# raspberry-pi-interface-board.net
KiCad netlist of a schematic drawn in EAGLE
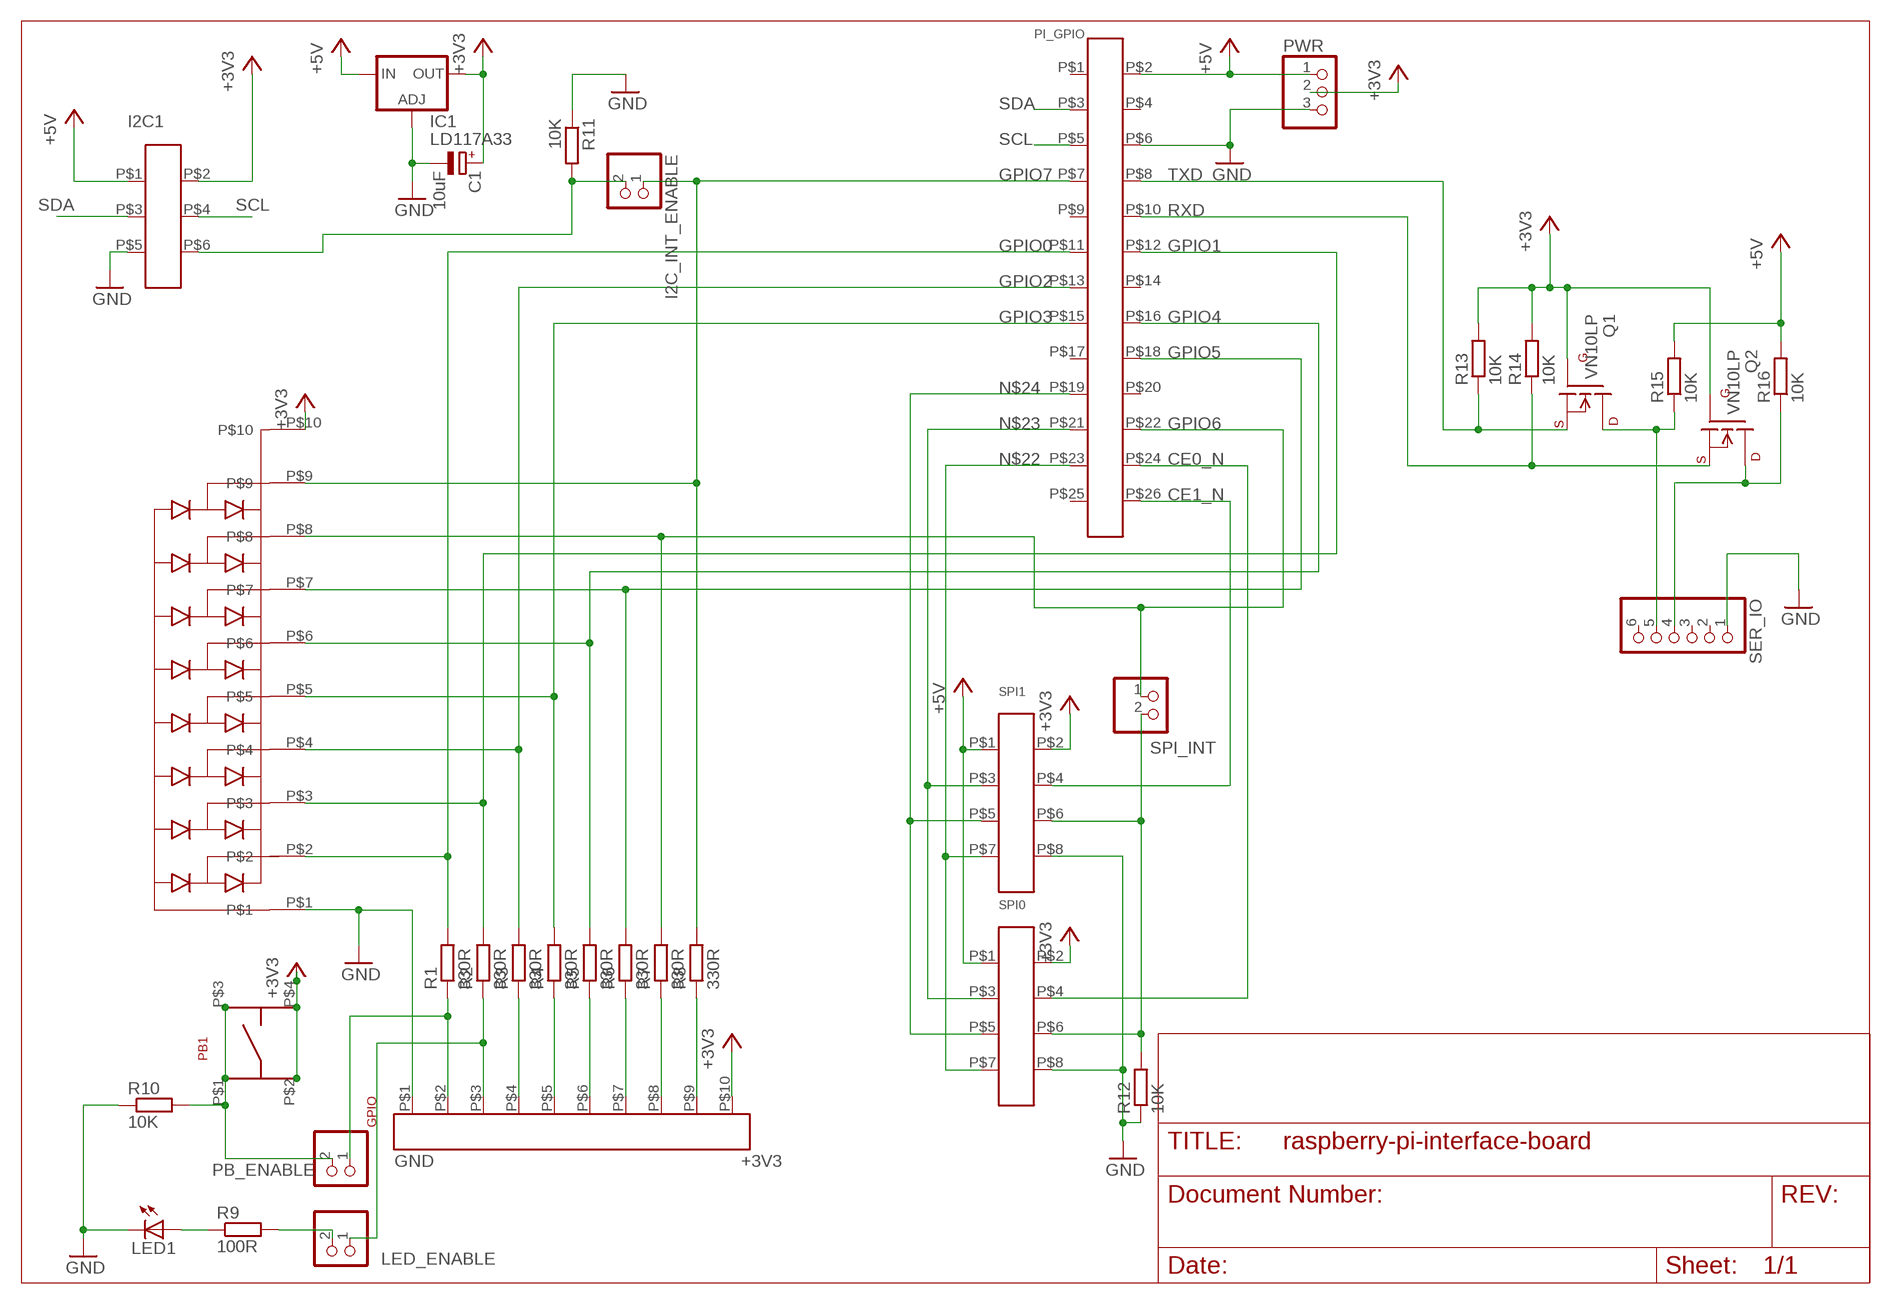
[diagram p0: schematic, sheet 1]

(export (version "E")
  (design (tool "Eeschema 10.0.6"))
  (components
    (comp (ref "C1")
      (value "10uF")
      (footprint "eagle-import:E2,5-7")
      (libsource (lib "eagle-import") (part "CPOL-EUE2.5-7"))
    )
    (comp (ref "GPIO")
      (value "APM-10W-SOCKET")
      (footprint "eagle-import:AMP-10W-SOCKET")
      (libsource (lib "eagle-import") (part "APM-10W-SOCKET"))
    )
    (comp (ref "I2C1")
      (value "IC2_0")
      (footprint "eagle-import:IDC-6W")
      (libsource (lib "eagle-import") (part "IDC-6W"))
    )
    (comp (ref "I2C_INT_ENABLE")
      (value "PINHD-1X2")
      (footprint "eagle-import:1X02")
      (libsource (lib "eagle-import") (part "PINHD-1X2"))
    )
    (comp (ref "IC1")
      (value "LD117A33")
      (footprint "eagle-import:TO220S")
      (libsource (lib "eagle-import") (part "LD117A?33"))
    )
    (comp (ref "LED1")
      (value "LED3MM")
      (footprint "eagle-import:LED3MM")
      (libsource (lib "eagle-import") (part "LED3MM"))
    )
    (comp (ref "LED_ENABLE")
      (value "PINHD-1X2")
      (footprint "eagle-import:1X02")
      (libsource (lib "eagle-import") (part "PINHD-1X2"))
    )
    (comp (ref "PB1")
      (value "TYCO-PUSHBUTTON")
      (footprint "eagle-import:TYCO-PUSHBUTTON")
      (libsource (lib "eagle-import") (part "TYCO-PUSHBUTTON"))
    )
    (comp (ref "PB_ENABLE")
      (value "PINHD-1X2")
      (footprint "eagle-import:1X02")
      (libsource (lib "eagle-import") (part "PINHD-1X2"))
    )
    (comp (ref "PI_GPIO")
      (value "IDC-26W")
      (footprint "eagle-import:IDC-26W")
      (libsource (lib "eagle-import") (part "IDC-26W"))
    )
    (comp (ref "PWR")
      (value "PINHD-1X3")
      (footprint "eagle-import:1X03")
      (libsource (lib "eagle-import") (part "PINHD-1X3"))
    )
    (comp (ref "Q1")
      (value "VN10LP")
      (footprint "eagle-import:TO92")
      (libsource (lib "eagle-import") (part "VN10LP"))
    )
    (comp (ref "Q2")
      (value "VN10LP")
      (footprint "eagle-import:TO92")
      (libsource (lib "eagle-import") (part "VN10LP"))
    )
    (comp (ref "R1")
      (value "330R")
      (footprint "eagle-import:0204_7")
      (libsource (lib "eagle-import") (part "R-EU_0204/7"))
    )
    (comp (ref "R2")
      (value "330R")
      (footprint "eagle-import:0204_7")
      (libsource (lib "eagle-import") (part "R-EU_0204/7"))
    )
    (comp (ref "R3")
      (value "330R")
      (footprint "eagle-import:0204_7")
      (libsource (lib "eagle-import") (part "R-EU_0204/7"))
    )
    (comp (ref "R4")
      (value "330R")
      (footprint "eagle-import:0204_7")
      (libsource (lib "eagle-import") (part "R-EU_0204/7"))
    )
    (comp (ref "R5")
      (value "330R")
      (footprint "eagle-import:0204_7")
      (libsource (lib "eagle-import") (part "R-EU_0204/7"))
    )
    (comp (ref "R6")
      (value "330R")
      (footprint "eagle-import:0204_7")
      (libsource (lib "eagle-import") (part "R-EU_0204/7"))
    )
    (comp (ref "R7")
      (value "330R")
      (footprint "eagle-import:0204_7")
      (libsource (lib "eagle-import") (part "R-EU_0204/7"))
    )
    (comp (ref "R8")
      (value "330R")
      (footprint "eagle-import:0204_7")
      (libsource (lib "eagle-import") (part "R-EU_0204/7"))
    )
    (comp (ref "R9")
      (value "100R")
      (footprint "eagle-import:0207_10")
      (libsource (lib "eagle-import") (part "R-EU_0207/10"))
    )
    (comp (ref "R10")
      (value "10K")
      (footprint "eagle-import:0207_10")
      (libsource (lib "eagle-import") (part "R-EU_0207/10"))
    )
    (comp (ref "R11")
      (value "10K")
      (footprint "eagle-import:0207_10")
      (libsource (lib "eagle-import") (part "R-EU_0207/10"))
    )
    (comp (ref "R12")
      (value "10K")
      (footprint "eagle-import:0207_10")
      (libsource (lib "eagle-import") (part "R-EU_0207/10"))
    )
    (comp (ref "R13")
      (value "10K")
      (footprint "eagle-import:0207_10")
      (libsource (lib "eagle-import") (part "R-EU_0207/10"))
    )
    (comp (ref "R14")
      (value "10K")
      (footprint "eagle-import:0207_10")
      (libsource (lib "eagle-import") (part "R-EU_0207/10"))
    )
    (comp (ref "R15")
      (value "10K")
      (footprint "eagle-import:0207_10")
      (libsource (lib "eagle-import") (part "R-EU_0207/10"))
    )
    (comp (ref "R16")
      (value "10K")
      (footprint "eagle-import:0207_10")
      (libsource (lib "eagle-import") (part "R-EU_0207/10"))
    )
    (comp (ref "SER_IO")
      (value "PINHD-1X6")
      (footprint "eagle-import:1X06")
      (libsource (lib "eagle-import") (part "PINHD-1X6"))
    )
    (comp (ref "SPI0")
      (value "IDC-8W")
      (footprint "eagle-import:IDC-8W")
      (libsource (lib "eagle-import") (part "IDC-8W"))
    )
    (comp (ref "SPI1")
      (value "IDC-8W")
      (footprint "eagle-import:IDC-8W")
      (libsource (lib "eagle-import") (part "IDC-8W"))
    )
    (comp (ref "SPI_INT")
      (value "PINHD-1X2")
      (footprint "eagle-import:1X02")
      (libsource (lib "eagle-import") (part "PINHD-1X2"))
    )
    (comp (ref "U$2")
      (value "D10-5A")
      (footprint "eagle-import:D10-5A")
      (libsource (lib "eagle-import") (part "D10-5A"))
    )
  )
  (nets
    (net (code "1") (name "+3V3") (class "Default")
      (node (ref "C1") (pin "+") (pinfunction "+_+") (pintype "passive"))
      (node (ref "GPIO") (pin "P$10") (pinfunction "P$10_P$10") (pintype "bidirectional"))
      (node (ref "I2C1") (pin "P$2") (pinfunction "P$2_P$2") (pintype "bidirectional"))
      (node (ref "IC1") (pin "2") (pinfunction "OUT_2") (pintype "passive"))
      (node (ref "PB1") (pin "P$2") (pinfunction "P$2_P$2") (pintype "bidirectional"))
      (node (ref "PB1") (pin "P$4") (pinfunction "P$4_P$4") (pintype "bidirectional"))
      (node (ref "PWR") (pin "2") (pinfunction "2_2") (pintype "passive"))
      (node (ref "Q1") (pin "2") (pinfunction "G_2") (pintype "passive"))
      (node (ref "Q2") (pin "2") (pinfunction "G_2") (pintype "passive"))
      (node (ref "R13") (pin "2") (pinfunction "2_2") (pintype "passive"))
      (node (ref "R14") (pin "2") (pinfunction "2_2") (pintype "passive"))
      (node (ref "SPI0") (pin "P$2") (pinfunction "P$2_P$2") (pintype "bidirectional"))
      (node (ref "SPI1") (pin "P$2") (pinfunction "P$2_P$2") (pintype "bidirectional"))
      (node (ref "U$2") (pin "P$10") (pinfunction "P$10_P$10") (pintype "power_in"))
    )
    (net (code "2") (name "+5V") (class "Default")
      (node (ref "I2C1") (pin "P$1") (pinfunction "P$1_P$1") (pintype "bidirectional"))
      (node (ref "IC1") (pin "3") (pinfunction "IN_3") (pintype "input"))
      (node (ref "PI_GPIO") (pin "P$2") (pinfunction "P$2_P$2") (pintype "bidirectional"))
      (node (ref "PWR") (pin "1") (pinfunction "1_1") (pintype "passive"))
      (node (ref "R15") (pin "2") (pinfunction "2_2") (pintype "passive"))
      (node (ref "R16") (pin "2") (pinfunction "2_2") (pintype "passive"))
      (node (ref "SPI0") (pin "P$1") (pinfunction "P$1_P$1") (pintype "bidirectional"))
      (node (ref "SPI1") (pin "P$1") (pinfunction "P$1_P$1") (pintype "bidirectional"))
    )
    (net (code "3") (name "/CE0_N") (class "Default")
      (node (ref "PI_GPIO") (pin "P$24") (pinfunction "P$24_P$24") (pintype "bidirectional"))
      (node (ref "SPI0") (pin "P$4") (pinfunction "P$4_P$4") (pintype "bidirectional"))
    )
    (net (code "4") (name "/CE1_N") (class "Default")
      (node (ref "PI_GPIO") (pin "P$26") (pinfunction "P$26_P$26") (pintype "bidirectional"))
      (node (ref "SPI1") (pin "P$4") (pinfunction "P$4_P$4") (pintype "bidirectional"))
    )
    (net (code "5") (name "/GPIO0") (class "Default")
      (node (ref "PI_GPIO") (pin "P$11") (pinfunction "P$11_P$11") (pintype "bidirectional"))
      (node (ref "R1") (pin "2") (pinfunction "2_2") (pintype "passive"))
      (node (ref "U$2") (pin "P$2") (pinfunction "P$2_P$2") (pintype "bidirectional"))
    )
    (net (code "6") (name "/GPIO1") (class "Default")
      (node (ref "PI_GPIO") (pin "P$12") (pinfunction "P$12_P$12") (pintype "bidirectional"))
      (node (ref "R2") (pin "2") (pinfunction "2_2") (pintype "passive"))
      (node (ref "U$2") (pin "P$3") (pinfunction "P$3_P$3") (pintype "bidirectional"))
    )
    (net (code "7") (name "/GPIO2") (class "Default")
      (node (ref "PI_GPIO") (pin "P$13") (pinfunction "P$13_P$13") (pintype "bidirectional"))
      (node (ref "R3") (pin "2") (pinfunction "2_2") (pintype "passive"))
      (node (ref "U$2") (pin "P$4") (pinfunction "P$4_P$4") (pintype "bidirectional"))
    )
    (net (code "8") (name "/GPIO3") (class "Default")
      (node (ref "PI_GPIO") (pin "P$15") (pinfunction "P$15_P$15") (pintype "bidirectional"))
      (node (ref "R4") (pin "2") (pinfunction "2_2") (pintype "passive"))
      (node (ref "U$2") (pin "P$5") (pinfunction "P$5_P$5") (pintype "bidirectional"))
    )
    (net (code "9") (name "/GPIO4") (class "Default")
      (node (ref "PI_GPIO") (pin "P$16") (pinfunction "P$16_P$16") (pintype "bidirectional"))
      (node (ref "R5") (pin "2") (pinfunction "2_2") (pintype "passive"))
      (node (ref "U$2") (pin "P$6") (pinfunction "P$6_P$6") (pintype "bidirectional"))
    )
    (net (code "10") (name "/GPIO5") (class "Default")
      (node (ref "PI_GPIO") (pin "P$18") (pinfunction "P$18_P$18") (pintype "bidirectional"))
      (node (ref "R6") (pin "2") (pinfunction "2_2") (pintype "passive"))
      (node (ref "U$2") (pin "P$7") (pinfunction "P$7_P$7") (pintype "bidirectional"))
    )
    (net (code "11") (name "/GPIO6") (class "Default")
      (node (ref "PI_GPIO") (pin "P$22") (pinfunction "P$22_P$22") (pintype "bidirectional"))
      (node (ref "R7") (pin "2") (pinfunction "2_2") (pintype "passive"))
      (node (ref "SPI_INT") (pin "1") (pinfunction "1_1") (pintype "passive"))
      (node (ref "U$2") (pin "P$8") (pinfunction "P$8_P$8") (pintype "bidirectional"))
    )
    (net (code "12") (name "/GPIO7") (class "Default")
      (node (ref "I2C_INT_ENABLE") (pin "1") (pinfunction "1_1") (pintype "passive"))
      (node (ref "PI_GPIO") (pin "P$7") (pinfunction "P$7_P$7") (pintype "bidirectional"))
      (node (ref "R8") (pin "2") (pinfunction "2_2") (pintype "passive"))
      (node (ref "U$2") (pin "P$9") (pinfunction "P$9_P$9") (pintype "bidirectional"))
    )
    (net (code "13") (name "/N$22") (class "Default")
      (node (ref "PI_GPIO") (pin "P$23") (pinfunction "P$23_P$23") (pintype "bidirectional"))
      (node (ref "SPI0") (pin "P$7") (pinfunction "P$7_P$7") (pintype "bidirectional"))
      (node (ref "SPI1") (pin "P$7") (pinfunction "P$7_P$7") (pintype "bidirectional"))
    )
    (net (code "14") (name "/N$23") (class "Default")
      (node (ref "PI_GPIO") (pin "P$21") (pinfunction "P$21_P$21") (pintype "bidirectional"))
      (node (ref "SPI0") (pin "P$3") (pinfunction "P$3_P$3") (pintype "bidirectional"))
      (node (ref "SPI1") (pin "P$3") (pinfunction "P$3_P$3") (pintype "bidirectional"))
    )
    (net (code "15") (name "/N$24") (class "Default")
      (node (ref "PI_GPIO") (pin "P$19") (pinfunction "P$19_P$19") (pintype "bidirectional"))
      (node (ref "SPI0") (pin "P$5") (pinfunction "P$5_P$5") (pintype "bidirectional"))
      (node (ref "SPI1") (pin "P$5") (pinfunction "P$5_P$5") (pintype "bidirectional"))
    )
    (net (code "16") (name "/RXD") (class "Default")
      (node (ref "PI_GPIO") (pin "P$10") (pinfunction "P$10_P$10") (pintype "bidirectional"))
      (node (ref "Q2") (pin "3") (pinfunction "S_3") (pintype "passive"))
      (node (ref "R14") (pin "1") (pinfunction "1_1") (pintype "passive"))
    )
    (net (code "17") (name "/SCL") (class "Default")
      (node (ref "I2C1") (pin "P$4") (pinfunction "P$4_P$4") (pintype "bidirectional"))
      (node (ref "PI_GPIO") (pin "P$5") (pinfunction "P$5_P$5") (pintype "bidirectional"))
    )
    (net (code "18") (name "/SDA") (class "Default")
      (node (ref "I2C1") (pin "P$3") (pinfunction "P$3_P$3") (pintype "bidirectional"))
      (node (ref "PI_GPIO") (pin "P$3") (pinfunction "P$3_P$3") (pintype "bidirectional"))
    )
    (net (code "19") (name "/TXD") (class "Default")
      (node (ref "PI_GPIO") (pin "P$8") (pinfunction "P$8_P$8") (pintype "bidirectional"))
      (node (ref "Q1") (pin "3") (pinfunction "S_3") (pintype "passive"))
      (node (ref "R13") (pin "1") (pinfunction "1_1") (pintype "passive"))
    )
    (net (code "20") (name "GND") (class "Default")
      (node (ref "C1") (pin "-") (pinfunction "-_-") (pintype "passive"))
      (node (ref "GPIO") (pin "P$1") (pinfunction "P$1_P$1") (pintype "bidirectional"))
      (node (ref "I2C1") (pin "P$5") (pinfunction "P$5_P$5") (pintype "bidirectional"))
      (node (ref "IC1") (pin "1") (pinfunction "ADJ_1") (pintype "input"))
      (node (ref "LED1") (pin "K") (pinfunction "C_K") (pintype "passive"))
      (node (ref "PI_GPIO") (pin "P$6") (pinfunction "P$6_P$6") (pintype "bidirectional"))
      (node (ref "PWR") (pin "3") (pinfunction "3_3") (pintype "passive"))
      (node (ref "R10") (pin "1") (pinfunction "1_1") (pintype "passive"))
      (node (ref "R11") (pin "1") (pinfunction "1_1") (pintype "passive"))
      (node (ref "R12") (pin "1") (pinfunction "1_1") (pintype "passive"))
      (node (ref "SER_IO") (pin "1") (pinfunction "1_1") (pintype "passive"))
      (node (ref "SPI0") (pin "P$8") (pinfunction "P$8_P$8") (pintype "bidirectional"))
      (node (ref "SPI1") (pin "P$8") (pinfunction "P$8_P$8") (pintype "bidirectional"))
      (node (ref "U$2") (pin "P$1") (pinfunction "P$1_P$1") (pintype "power_in"))
    )
    (net (code "21") (name "Net-(GPIO-PadP$2)") (class "Default")
      (node (ref "GPIO") (pin "P$2") (pinfunction "P$2_P$2") (pintype "bidirectional"))
      (node (ref "PB_ENABLE") (pin "1") (pinfunction "1_1") (pintype "passive"))
      (node (ref "R1") (pin "1") (pinfunction "1_1") (pintype "passive"))
    )
    (net (code "22") (name "Net-(GPIO-PadP$3)") (class "Default")
      (node (ref "GPIO") (pin "P$3") (pinfunction "P$3_P$3") (pintype "bidirectional"))
      (node (ref "LED_ENABLE") (pin "1") (pinfunction "1_1") (pintype "passive"))
      (node (ref "R2") (pin "1") (pinfunction "1_1") (pintype "passive"))
    )
    (net (code "23") (name "Net-(GPIO-PadP$4)") (class "Default")
      (node (ref "GPIO") (pin "P$4") (pinfunction "P$4_P$4") (pintype "bidirectional"))
      (node (ref "R3") (pin "1") (pinfunction "1_1") (pintype "passive"))
    )
    (net (code "24") (name "Net-(GPIO-PadP$5)") (class "Default")
      (node (ref "GPIO") (pin "P$5") (pinfunction "P$5_P$5") (pintype "bidirectional"))
      (node (ref "R4") (pin "1") (pinfunction "1_1") (pintype "passive"))
    )
    (net (code "25") (name "Net-(GPIO-PadP$6)") (class "Default")
      (node (ref "GPIO") (pin "P$6") (pinfunction "P$6_P$6") (pintype "bidirectional"))
      (node (ref "R5") (pin "1") (pinfunction "1_1") (pintype "passive"))
    )
    (net (code "26") (name "Net-(GPIO-PadP$7)") (class "Default")
      (node (ref "GPIO") (pin "P$7") (pinfunction "P$7_P$7") (pintype "bidirectional"))
      (node (ref "R6") (pin "1") (pinfunction "1_1") (pintype "passive"))
    )
    (net (code "27") (name "Net-(GPIO-PadP$8)") (class "Default")
      (node (ref "GPIO") (pin "P$8") (pinfunction "P$8_P$8") (pintype "bidirectional"))
      (node (ref "R7") (pin "1") (pinfunction "1_1") (pintype "passive"))
    )
    (net (code "28") (name "Net-(GPIO-PadP$9)") (class "Default")
      (node (ref "GPIO") (pin "P$9") (pinfunction "P$9_P$9") (pintype "bidirectional"))
      (node (ref "R8") (pin "1") (pinfunction "1_1") (pintype "passive"))
    )
    (net (code "29") (name "Net-(I2C1-PadP$6)") (class "Default")
      (node (ref "I2C1") (pin "P$6") (pinfunction "P$6_P$6") (pintype "bidirectional"))
      (node (ref "I2C_INT_ENABLE") (pin "2") (pinfunction "2_2") (pintype "passive"))
      (node (ref "R11") (pin "2") (pinfunction "2_2") (pintype "passive"))
    )
    (net (code "30") (name "Net-(LED1-PadA)") (class "Default")
      (node (ref "LED1") (pin "A") (pinfunction "A_A") (pintype "passive"))
      (node (ref "R9") (pin "1") (pinfunction "1_1") (pintype "passive"))
    )
    (net (code "31") (name "Net-(LED_ENABLE-Pad2)") (class "Default")
      (node (ref "LED_ENABLE") (pin "2") (pinfunction "2_2") (pintype "passive"))
      (node (ref "R9") (pin "2") (pinfunction "2_2") (pintype "passive"))
    )
    (net (code "32") (name "Net-(PB1-PadP$1)") (class "Default")
      (node (ref "PB1") (pin "P$1") (pinfunction "P$1_P$1") (pintype "bidirectional"))
      (node (ref "PB1") (pin "P$3") (pinfunction "P$3_P$3") (pintype "bidirectional"))
      (node (ref "PB_ENABLE") (pin "2") (pinfunction "2_2") (pintype "passive"))
      (node (ref "R10") (pin "2") (pinfunction "2_2") (pintype "passive"))
    )
    (net (code "33") (name "Net-(Q1-D)") (class "Default")
      (node (ref "Q1") (pin "1") (pinfunction "D_1") (pintype "passive"))
      (node (ref "R15") (pin "1") (pinfunction "1_1") (pintype "passive"))
      (node (ref "SER_IO") (pin "5") (pinfunction "5_5") (pintype "passive"))
    )
    (net (code "34") (name "Net-(Q2-D)") (class "Default")
      (node (ref "Q2") (pin "1") (pinfunction "D_1") (pintype "passive"))
      (node (ref "R16") (pin "1") (pinfunction "1_1") (pintype "passive"))
      (node (ref "SER_IO") (pin "4") (pinfunction "4_4") (pintype "passive"))
    )
    (net (code "35") (name "Net-(R12-Pad2)") (class "Default")
      (node (ref "R12") (pin "2") (pinfunction "2_2") (pintype "passive"))
      (node (ref "SPI0") (pin "P$6") (pinfunction "P$6_P$6") (pintype "bidirectional"))
      (node (ref "SPI1") (pin "P$6") (pinfunction "P$6_P$6") (pintype "bidirectional"))
      (node (ref "SPI_INT") (pin "2") (pinfunction "2_2") (pintype "passive"))
    )
    (net (code "36") (name "unconnected-(PI_GPIO-PadP$1)") (class "Default")
      (node (ref "PI_GPIO") (pin "P$1") (pinfunction "P$1_P$1") (pintype "bidirectional"))
    )
    (net (code "37") (name "unconnected-(PI_GPIO-PadP$4)") (class "Default")
      (node (ref "PI_GPIO") (pin "P$4") (pinfunction "P$4_P$4") (pintype "bidirectional"))
    )
    (net (code "38") (name "unconnected-(PI_GPIO-PadP$9)") (class "Default")
      (node (ref "PI_GPIO") (pin "P$9") (pinfunction "P$9_P$9") (pintype "bidirectional"))
    )
    (net (code "39") (name "unconnected-(PI_GPIO-PadP$14)") (class "Default")
      (node (ref "PI_GPIO") (pin "P$14") (pinfunction "P$14_P$14") (pintype "bidirectional"))
    )
    (net (code "40") (name "unconnected-(PI_GPIO-PadP$17)") (class "Default")
      (node (ref "PI_GPIO") (pin "P$17") (pinfunction "P$17_P$17") (pintype "bidirectional"))
    )
    (net (code "41") (name "unconnected-(PI_GPIO-PadP$20)") (class "Default")
      (node (ref "PI_GPIO") (pin "P$20") (pinfunction "P$20_P$20") (pintype "bidirectional"))
    )
    (net (code "42") (name "unconnected-(PI_GPIO-PadP$25)") (class "Default")
      (node (ref "PI_GPIO") (pin "P$25") (pinfunction "P$25_P$25") (pintype "bidirectional"))
    )
    (net (code "43") (name "unconnected-(SER_IO-Pad2)") (class "Default")
      (node (ref "SER_IO") (pin "2") (pinfunction "2_2") (pintype "passive"))
    )
    (net (code "44") (name "unconnected-(SER_IO-Pad3)") (class "Default")
      (node (ref "SER_IO") (pin "3") (pinfunction "3_3") (pintype "passive"))
    )
    (net (code "45") (name "unconnected-(SER_IO-Pad6)") (class "Default")
      (node (ref "SER_IO") (pin "6") (pinfunction "6_6") (pintype "passive"))
    )
  )
)
